# CAN_MAX3051.net
KiCad netlist of a schematic drawn in Altium Designer
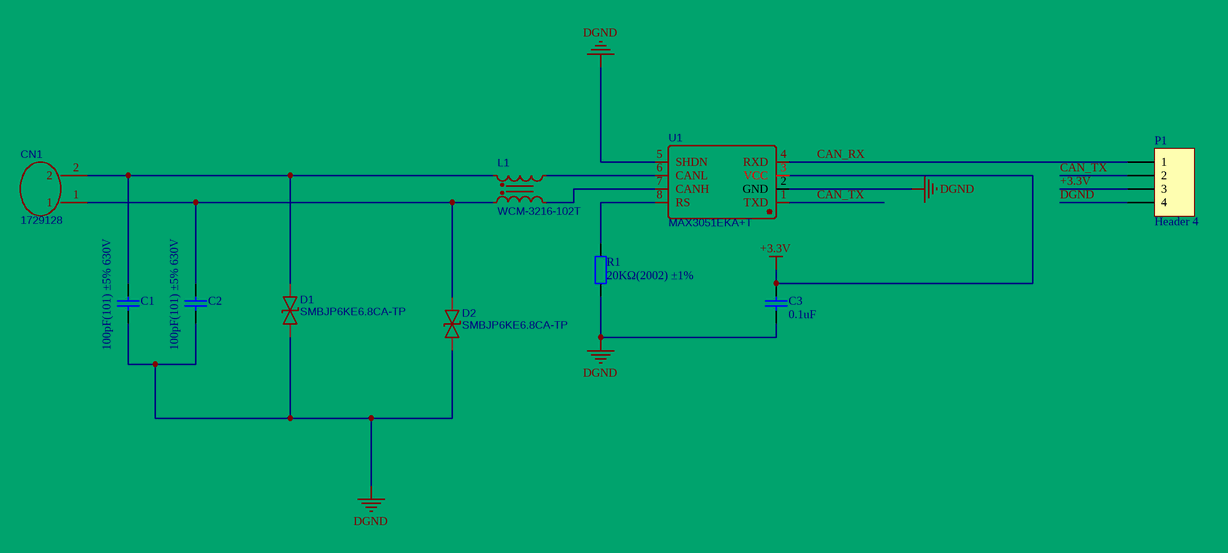
[diagram p0: CAN_MAX3051.SchDoc]

(export (version "E")
  (design (tool "Eeschema 10.0.6"))
  (components
    (comp (ref "C1")
      (value "100pF(101) ±5% 630V")
      (footprint "0805_C")
      (description "贴片电容")
      (fields (field (name "BOM_MANUFACTURER PART") "GRM21A5C2J101JWA1D"))
      (libsource (lib "Miscellaneous Devices LC") (part "0805 1uF (105) 10% 50V"))
    )
    (comp (ref "C2")
      (value "100pF(101) ±5% 630V")
      (footprint "0805_C")
      (description "贴片电容")
      (fields (field (name "BOM_MANUFACTURER PART") "GRM21A5C2J101JWA1D"))
      (libsource (lib "Miscellaneous Devices LC") (part "0805 1uF (105) 10% 50V"))
    )
    (comp (ref "C3")
      (value "0.1uF")
      (footprint "0805_C")
      (description "贴片电容")
      (libsource (lib "Miscellaneous Devices LC") (part "0805 1uF (105) 10% 50V"))
    )
    (comp (ref "CN1")
      (value "1729128")
      (footprint "CONN-TH_2P-P5.08_1714984")
      (libsource (lib "Miscellaneous Devices LC") (part "MKDSN1.5/2-5.08"))
    )
    (comp (ref "D1")
      (value "SMBJP6KE6.8CA-TP")
      (footprint "SMB_L4.6-W3.6-LS5.3-BI")
      (libsource (lib "Miscellaneous Devices LC") (part "SMBJP6KE6.8CA-TP"))
    )
    (comp (ref "D2")
      (value "SMBJP6KE6.8CA-TP")
      (footprint "SMB_L4.6-W3.6-LS5.3-BI")
      (libsource (lib "Miscellaneous Devices LC") (part "SMBJP6KE6.8CA-TP"))
    )
    (comp (ref "L1")
      (value "WCM-3216-102T")
      (footprint "FILTER-SMD_1206-4P-L3.2-W1.6-BL-CW")
      (libsource (lib "Miscellaneous Devices LC") (part "WCM-3216-102T"))
    )
    (comp (ref "P1")
      (value "Header 4")
      (footprint "HDR1X4")
      (description "Header, 4-Pin")
      (fields (field (name "PUBLISHER") "Altium Limited"))
      (libsource (lib "Miscellaneous Connectors") (part "Header 4"))
    )
    (comp (ref "R1")
      (value "20KΩ(2002) ±1%")
      (footprint "0805_R")
      (description "贴片电阻")
      (fields (field (name "BOM_MANUFACTURER PART") "MCR10EZPF2002"))
      (libsource (lib "Miscellaneous Devices LC") (part "0805 1KΩ (1001) 1%"))
    )
    (comp (ref "U1")
      (value "MAX3051EKA+T")
      (footprint "SOT-23-8_L3.0-W1.7-P0.65-LS2.8-TL")
      (libsource (lib "Miscellaneous Devices LC") (part "MAX3051EKA"))
    )
  )
  (nets
    (net (code "1") (name "+3.3V") (class "Default")
      (node (ref "C3") (pin "2") (pinfunction "2_2") (pintype "passive"))
      (node (ref "P1") (pin "3") (pinfunction "3_3") (pintype "passive"))
      (node (ref "U1") (pin "3") (pinfunction "VCC_3") (pintype "passive"))
    )
    (net (code "2") (name "/CAN_RX") (class "Default")
      (node (ref "P1") (pin "1") (pinfunction "1_1") (pintype "passive"))
      (node (ref "U1") (pin "4") (pinfunction "RXD_4") (pintype "passive"))
    )
    (net (code "3") (name "/CAN_TX") (class "Default")
      (node (ref "P1") (pin "2") (pinfunction "2_2") (pintype "passive"))
      (node (ref "U1") (pin "1") (pinfunction "TXD_1") (pintype "passive"))
    )
    (net (code "4") (name "DGND") (class "Default")
      (node (ref "C1") (pin "1") (pinfunction "1_1") (pintype "passive"))
      (node (ref "C2") (pin "1") (pinfunction "1_1") (pintype "passive"))
      (node (ref "C3") (pin "1") (pinfunction "1_1") (pintype "passive"))
      (node (ref "D1") (pin "1") (pinfunction "1_1") (pintype "passive"))
      (node (ref "D2") (pin "1") (pinfunction "1_1") (pintype "passive"))
      (node (ref "P1") (pin "4") (pinfunction "4_4") (pintype "passive"))
      (node (ref "R1") (pin "1") (pinfunction "1_1") (pintype "passive"))
      (node (ref "U1") (pin "2") (pinfunction "GND_2") (pintype "passive"))
      (node (ref "U1") (pin "5") (pinfunction "SHDN_5") (pintype "passive"))
    )
    (net (code "5") (name "Net-(C1-Pad2)") (class "Default")
      (node (ref "C1") (pin "2") (pinfunction "2_2") (pintype "passive"))
      (node (ref "CN1") (pin "2") (pinfunction "2_2") (pintype "passive"))
      (node (ref "D1") (pin "2") (pinfunction "2_2") (pintype "passive"))
      (node (ref "L1") (pin "1") (pinfunction "1_1") (pintype "passive"))
    )
    (net (code "6") (name "Net-(C2-Pad2)") (class "Default")
      (node (ref "C2") (pin "2") (pinfunction "2_2") (pintype "passive"))
      (node (ref "CN1") (pin "1") (pinfunction "1_1") (pintype "passive"))
      (node (ref "D2") (pin "2") (pinfunction "2_2") (pintype "passive"))
      (node (ref "L1") (pin "2") (pinfunction "2_2") (pintype "passive"))
    )
    (net (code "7") (name "Net-(U1-CANH)") (class "Default")
      (node (ref "L1") (pin "3") (pinfunction "3_3") (pintype "passive"))
      (node (ref "U1") (pin "7") (pinfunction "CANH_7") (pintype "passive"))
    )
    (net (code "8") (name "Net-(U1-CANL)") (class "Default")
      (node (ref "L1") (pin "4") (pinfunction "4_4") (pintype "passive"))
      (node (ref "U1") (pin "6") (pinfunction "CANL_6") (pintype "passive"))
    )
    (net (code "9") (name "Net-(U1-RS)") (class "Default")
      (node (ref "R1") (pin "2") (pinfunction "2_2") (pintype "passive"))
      (node (ref "U1") (pin "8") (pinfunction "RS_8") (pintype "passive"))
    )
  )
)
